# dummy-load_-_OK.net
KiCad netlist of a schematic drawn in EAGLE
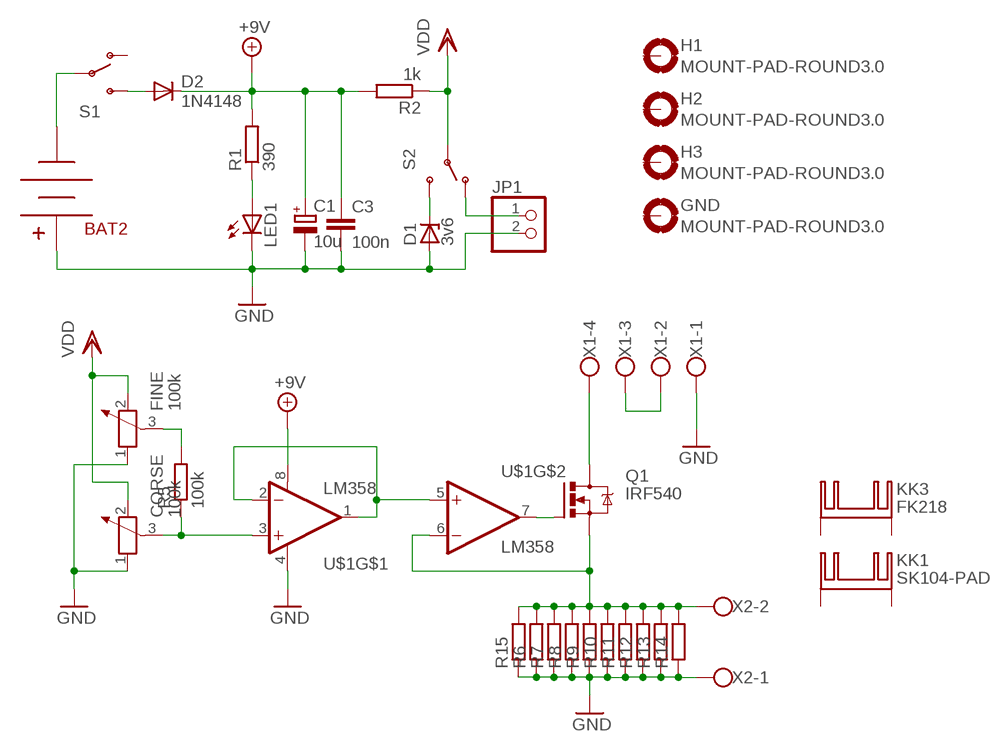
[diagram p0: schematic, sheet 1]

(export (version "E")
  (design (tool "Eeschema 10.0.6"))
  (components
    (comp (ref "BAT2")
      (value "BC9VPC")
      (footprint "eagle-import:BC9VPC")
      (libsource (lib "eagle-import") (part "BC9VPC"))
    )
    (comp (ref "C1")
      (value "10u")
      (footprint "eagle-import:TT2D5L")
      (libsource (lib "eagle-import") (part "CPOL-EUTT2D5L"))
    )
    (comp (ref "C3")
      (value "100n")
      (footprint "eagle-import:C025-025X050")
      (libsource (lib "eagle-import") (part "C-EU025-025X050"))
    )
    (comp (ref "CORSE")
      (value "100k")
      (footprint "eagle-import:PT-10")
      (libsource (lib "eagle-import") (part "POTENTIOMETER_PT-10"))
    )
    (comp (ref "D1")
      (value "3v6")
      (footprint "eagle-import:ZDIO-5")
      (libsource (lib "eagle-import") (part "ZENER-DIODEZD-5"))
    )
    (comp (ref "D2")
      (value "1N4148")
      (footprint "eagle-import:D-2.5")
      (libsource (lib "eagle-import") (part "DIODE-D-2.5"))
    )
    (comp (ref "FINE")
      (value "100k")
      (footprint "eagle-import:PT-10")
      (libsource (lib "eagle-import") (part "POTENTIOMETER_PT-10"))
    )
    (comp (ref "GND")
      (value "MOUNT-PAD-ROUND3.0")
      (footprint "eagle-import:3,0-PAD")
      (libsource (lib "eagle-import") (part "MOUNT-PAD-ROUND3.0"))
    )
    (comp (ref "H1")
      (value "MOUNT-PAD-ROUND3.0")
      (footprint "eagle-import:3,0-PAD")
      (libsource (lib "eagle-import") (part "MOUNT-PAD-ROUND3.0"))
    )
    (comp (ref "H2")
      (value "MOUNT-PAD-ROUND3.0")
      (footprint "eagle-import:3,0-PAD")
      (libsource (lib "eagle-import") (part "MOUNT-PAD-ROUND3.0"))
    )
    (comp (ref "H3")
      (value "MOUNT-PAD-ROUND3.0")
      (footprint "eagle-import:3,0-PAD")
      (libsource (lib "eagle-import") (part "MOUNT-PAD-ROUND3.0"))
    )
    (comp (ref "JP1")
      (value "PINHD-1X2")
      (footprint "eagle-import:1X02")
      (libsource (lib "eagle-import") (part "PINHD-1X2"))
    )
    (comp (ref "KK1")
      (value "SK104-PAD")
      (footprint "eagle-import:SK104-PAD")
      (libsource (lib "eagle-import") (part "SK104-PAD"))
    )
    (comp (ref "KK3")
      (value "FK218")
      (footprint "eagle-import:FK218")
      (libsource (lib "eagle-import") (part "FK218"))
    )
    (comp (ref "LED1")
      (value "LED5MM")
      (footprint "eagle-import:LED5MM")
      (libsource (lib "eagle-import") (part "LED5MM"))
    )
    (comp (ref "Q1")
      (value "IRF540")
      (footprint "eagle-import:TO220BV")
      (libsource (lib "eagle-import") (part "IRF540"))
    )
    (comp (ref "R1")
      (value "390")
      (footprint "eagle-import:0207_2V")
      (libsource (lib "eagle-import") (part "R-EU_0207/2V"))
    )
    (comp (ref "R2")
      (value "1k")
      (footprint "eagle-import:0204_7")
      (libsource (lib "eagle-import") (part "R-EU_0204/7"))
    )
    (comp (ref "R5")
      (value "100k")
      (footprint "eagle-import:0204_7")
      (libsource (lib "eagle-import") (part "R-EU_0204/7"))
    )
    (comp (ref "R6")
      (value "R-EU_0207/7")
      (footprint "eagle-import:0207_7")
      (libsource (lib "eagle-import") (part "R-EU_0207/7"))
    )
    (comp (ref "R7")
      (value "R-EU_0207/7")
      (footprint "eagle-import:0207_7")
      (libsource (lib "eagle-import") (part "R-EU_0207/7"))
    )
    (comp (ref "R8")
      (value "R-EU_0207/7")
      (footprint "eagle-import:0207_7")
      (libsource (lib "eagle-import") (part "R-EU_0207/7"))
    )
    (comp (ref "R9")
      (value "R-EU_0207/7")
      (footprint "eagle-import:0207_7")
      (libsource (lib "eagle-import") (part "R-EU_0207/7"))
    )
    (comp (ref "R10")
      (value "R-EU_0207/7")
      (footprint "eagle-import:0207_7")
      (libsource (lib "eagle-import") (part "R-EU_0207/7"))
    )
    (comp (ref "R11")
      (value "R-EU_0207/7")
      (footprint "eagle-import:0207_7")
      (libsource (lib "eagle-import") (part "R-EU_0207/7"))
    )
    (comp (ref "R12")
      (value "R-EU_0207/7")
      (footprint "eagle-import:0207_7")
      (libsource (lib "eagle-import") (part "R-EU_0207/7"))
    )
    (comp (ref "R13")
      (value "R-EU_0207/7")
      (footprint "eagle-import:0207_7")
      (libsource (lib "eagle-import") (part "R-EU_0207/7"))
    )
    (comp (ref "R14")
      (value "R-EU_0207/7")
      (footprint "eagle-import:0207_7")
      (libsource (lib "eagle-import") (part "R-EU_0207/7"))
    )
    (comp (ref "R15")
      (value "R-EU_0207/7")
      (footprint "eagle-import:0207_7")
      (libsource (lib "eagle-import") (part "R-EU_0207/7"))
    )
    (comp (ref "S1")
      (value "SWITCH-SPSTPTH")
      (footprint "eagle-import:SWITCH-SPDT")
      (libsource (lib "eagle-import") (part "SWITCH-SPSTPTH"))
    )
    (comp (ref "S2")
      (value "SWITCH-SPSTPTH")
      (footprint "eagle-import:SWITCH-SPDT")
      (libsource (lib "eagle-import") (part "SWITCH-SPSTPTH"))
    )
    (comp (ref "U$1")
      (value "LM358")
      (footprint "eagle-import:DIP08")
      (libsource (lib "eagle-import") (part "LM358"))
    )
    (comp (ref "X1")
      (value "W237-4")
      (footprint "eagle-import:W237-4")
      (libsource (lib "eagle-import") (part "W237-4"))
    )
    (comp (ref "X2")
      (value "W237-102")
      (footprint "eagle-import:W237-102")
      (fields (field (name "MPN") "237-102"))
      (libsource (lib "eagle-import") (part "W237-102"))
    )
  )
  (nets
    (net (code "1") (name "+9V") (class "Default")
      (node (ref "C1") (pin "+") (pinfunction "+_+") (pintype "passive"))
      (node (ref "C3") (pin "1") (pinfunction "1_1") (pintype "passive"))
      (node (ref "D2") (pin "C") (pinfunction "C_C") (pintype "passive"))
      (node (ref "R1") (pin "2") (pinfunction "2_2") (pintype "passive"))
      (node (ref "R2") (pin "2") (pinfunction "2_2") (pintype "passive"))
      (node (ref "U$1") (pin "8") (pinfunction "V+_8") (pintype "power_in"))
    )
    (net (code "2") (name "GND") (class "Default")
      (node (ref "BAT2") (pin "V+") (pinfunction "V+_V+") (pintype "bidirectional"))
      (node (ref "C1") (pin "-") (pinfunction "-_-") (pintype "passive"))
      (node (ref "C3") (pin "2") (pinfunction "2_2") (pintype "passive"))
      (node (ref "CORSE") (pin "1") (pinfunction "1_1") (pintype "passive"))
      (node (ref "D1") (pin "A") (pinfunction "A_A") (pintype "passive"))
      (node (ref "FINE") (pin "1") (pinfunction "1_1") (pintype "passive"))
      (node (ref "JP1") (pin "2") (pinfunction "2_2") (pintype "passive"))
      (node (ref "LED1") (pin "K") (pinfunction "C_K") (pintype "passive"))
      (node (ref "R10") (pin "1") (pinfunction "1_1") (pintype "passive"))
      (node (ref "R11") (pin "1") (pinfunction "1_1") (pintype "passive"))
      (node (ref "R12") (pin "1") (pinfunction "1_1") (pintype "passive"))
      (node (ref "R13") (pin "1") (pinfunction "1_1") (pintype "passive"))
      (node (ref "R14") (pin "1") (pinfunction "1_1") (pintype "passive"))
      (node (ref "R15") (pin "1") (pinfunction "1_1") (pintype "passive"))
      (node (ref "R6") (pin "1") (pinfunction "1_1") (pintype "passive"))
      (node (ref "R7") (pin "1") (pinfunction "1_1") (pintype "passive"))
      (node (ref "R8") (pin "1") (pinfunction "1_1") (pintype "passive"))
      (node (ref "R9") (pin "1") (pinfunction "1_1") (pintype "passive"))
      (node (ref "U$1") (pin "4") (pinfunction "V-_4") (pintype "power_in"))
      (node (ref "X1") (pin "1") (pinfunction "KL_1") (pintype "passive"))
      (node (ref "X2") (pin "1") (pinfunction "KL_1") (pintype "passive"))
    )
    (net (code "3") (name "Net-(FINE-Pad3)") (class "Default")
      (node (ref "FINE") (pin "3") (pinfunction "3_3") (pintype "passive"))
      (node (ref "R5") (pin "2") (pinfunction "2_2") (pintype "passive"))
    )
    (net (code "4") (name "Net-(LED1-PadA)") (class "Default")
      (node (ref "LED1") (pin "A") (pinfunction "A_A") (pintype "passive"))
      (node (ref "R1") (pin "1") (pinfunction "1_1") (pintype "passive"))
    )
    (net (code "5") (name "Net-(S1-P)") (class "Default")
      (node (ref "BAT2") (pin "V-") (pinfunction "V-_V-") (pintype "bidirectional"))
      (node (ref "S1") (pin "2") (pinfunction "P_2") (pintype "passive"))
    )
    (net (code "6") (name "Net-(S1-S)") (class "Default")
      (node (ref "D2") (pin "A") (pinfunction "A_A") (pintype "passive"))
      (node (ref "S1") (pin "3") (pinfunction "S_3") (pintype "passive"))
    )
    (net (code "7") (name "Net-(S2-O)") (class "Default")
      (node (ref "JP1") (pin "1") (pinfunction "1_1") (pintype "passive"))
      (node (ref "S2") (pin "1") (pinfunction "O_1") (pintype "passive"))
    )
    (net (code "8") (name "Net-(S2-S)") (class "Default")
      (node (ref "D1") (pin "C") (pinfunction "C_C") (pintype "passive"))
      (node (ref "S2") (pin "3") (pinfunction "S_3") (pintype "passive"))
    )
    (net (code "9") (name "Net-(U$1A-+IN)") (class "Default")
      (node (ref "CORSE") (pin "3") (pinfunction "3_3") (pintype "passive"))
      (node (ref "R5") (pin "1") (pinfunction "1_1") (pintype "passive"))
      (node (ref "U$1") (pin "3") (pinfunction "+IN_3") (pintype "input"))
    )
    (net (code "10") (name "Net-(U$1A--IN)") (class "Default")
      (node (ref "U$1") (pin "1") (pinfunction "OUT_1") (pintype "output"))
      (node (ref "U$1") (pin "2") (pinfunction "-IN_2") (pintype "input"))
      (node (ref "U$1") (pin "5") (pinfunction "+IN_5") (pintype "input"))
    )
    (net (code "11") (name "Net-(U$1B--IN)") (class "Default")
      (node (ref "Q1") (pin "S") (pinfunction "S_S") (pintype "passive"))
      (node (ref "R10") (pin "2") (pinfunction "2_2") (pintype "passive"))
      (node (ref "R11") (pin "2") (pinfunction "2_2") (pintype "passive"))
      (node (ref "R12") (pin "2") (pinfunction "2_2") (pintype "passive"))
      (node (ref "R13") (pin "2") (pinfunction "2_2") (pintype "passive"))
      (node (ref "R14") (pin "2") (pinfunction "2_2") (pintype "passive"))
      (node (ref "R15") (pin "2") (pinfunction "2_2") (pintype "passive"))
      (node (ref "R6") (pin "2") (pinfunction "2_2") (pintype "passive"))
      (node (ref "R7") (pin "2") (pinfunction "2_2") (pintype "passive"))
      (node (ref "R8") (pin "2") (pinfunction "2_2") (pintype "passive"))
      (node (ref "R9") (pin "2") (pinfunction "2_2") (pintype "passive"))
      (node (ref "U$1") (pin "6") (pinfunction "-IN_6") (pintype "input"))
      (node (ref "X2") (pin "2") (pinfunction "KL_2") (pintype "passive"))
    )
    (net (code "12") (name "Net-(U$1B-OUT)") (class "Default")
      (node (ref "Q1") (pin "G") (pinfunction "G_G") (pintype "passive"))
      (node (ref "U$1") (pin "7") (pinfunction "OUT_7") (pintype "output"))
    )
    (net (code "13") (name "Net-(X1B-KL)") (class "Default")
      (node (ref "X1") (pin "2") (pinfunction "KL_2") (pintype "passive"))
      (node (ref "X1") (pin "3") (pinfunction "KL_3") (pintype "passive"))
    )
    (net (code "14") (name "Net-(X1D-KL)") (class "Default")
      (node (ref "Q1") (pin "D") (pinfunction "D_D") (pintype "passive"))
      (node (ref "X1") (pin "4") (pinfunction "KL_4") (pintype "passive"))
    )
    (net (code "15") (name "VDD") (class "Default")
      (node (ref "CORSE") (pin "2") (pinfunction "2_2") (pintype "passive"))
      (node (ref "FINE") (pin "2") (pinfunction "2_2") (pintype "passive"))
      (node (ref "R2") (pin "1") (pinfunction "1_1") (pintype "passive"))
      (node (ref "S2") (pin "2") (pinfunction "P_2") (pintype "passive"))
    )
    (net (code "16") (name "unconnected-(GND-MOUNT-PadB3,0)") (class "Default")
      (node (ref "GND") (pin "B3,0") (pinfunction "MOUNT_B3,0") (pintype "passive"))
    )
    (net (code "17") (name "unconnected-(H1-MOUNT-PadB3,0)") (class "Default")
      (node (ref "H1") (pin "B3,0") (pinfunction "MOUNT_B3,0") (pintype "passive"))
    )
    (net (code "18") (name "unconnected-(H2-MOUNT-PadB3,0)") (class "Default")
      (node (ref "H2") (pin "B3,0") (pinfunction "MOUNT_B3,0") (pintype "passive"))
    )
    (net (code "19") (name "unconnected-(H3-MOUNT-PadB3,0)") (class "Default")
      (node (ref "H3") (pin "B3,0") (pinfunction "MOUNT_B3,0") (pintype "passive"))
    )
    (net (code "20") (name "unconnected-(KK1-K-PadK1)") (class "Default")
      (node (ref "KK1") (pin "K1") (pinfunction "K_K1") (pintype "passive"))
    )
    (net (code "21") (name "unconnected-(KK1-K-PadK2)") (class "Default")
      (node (ref "KK1") (pin "K2") (pinfunction "K_K2") (pintype "passive"))
    )
    (net (code "22") (name "unconnected-(KK3-K-PadA2,2)") (class "Default")
      (node (ref "KK3") (pin "A2,2") (pinfunction "K_A2,2") (pintype "passive"))
    )
    (net (code "23") (name "unconnected-(KK3-K-PadB2,2)") (class "Default")
      (node (ref "KK3") (pin "B2,2") (pinfunction "K_B2,2") (pintype "passive"))
    )
    (net (code "24") (name "unconnected-(S1-O-Pad1)") (class "Default")
      (node (ref "S1") (pin "1") (pinfunction "O_1") (pintype "passive"))
    )
  )
)
